# working.net
KiCad netlist of a schematic drawn in EAGLE
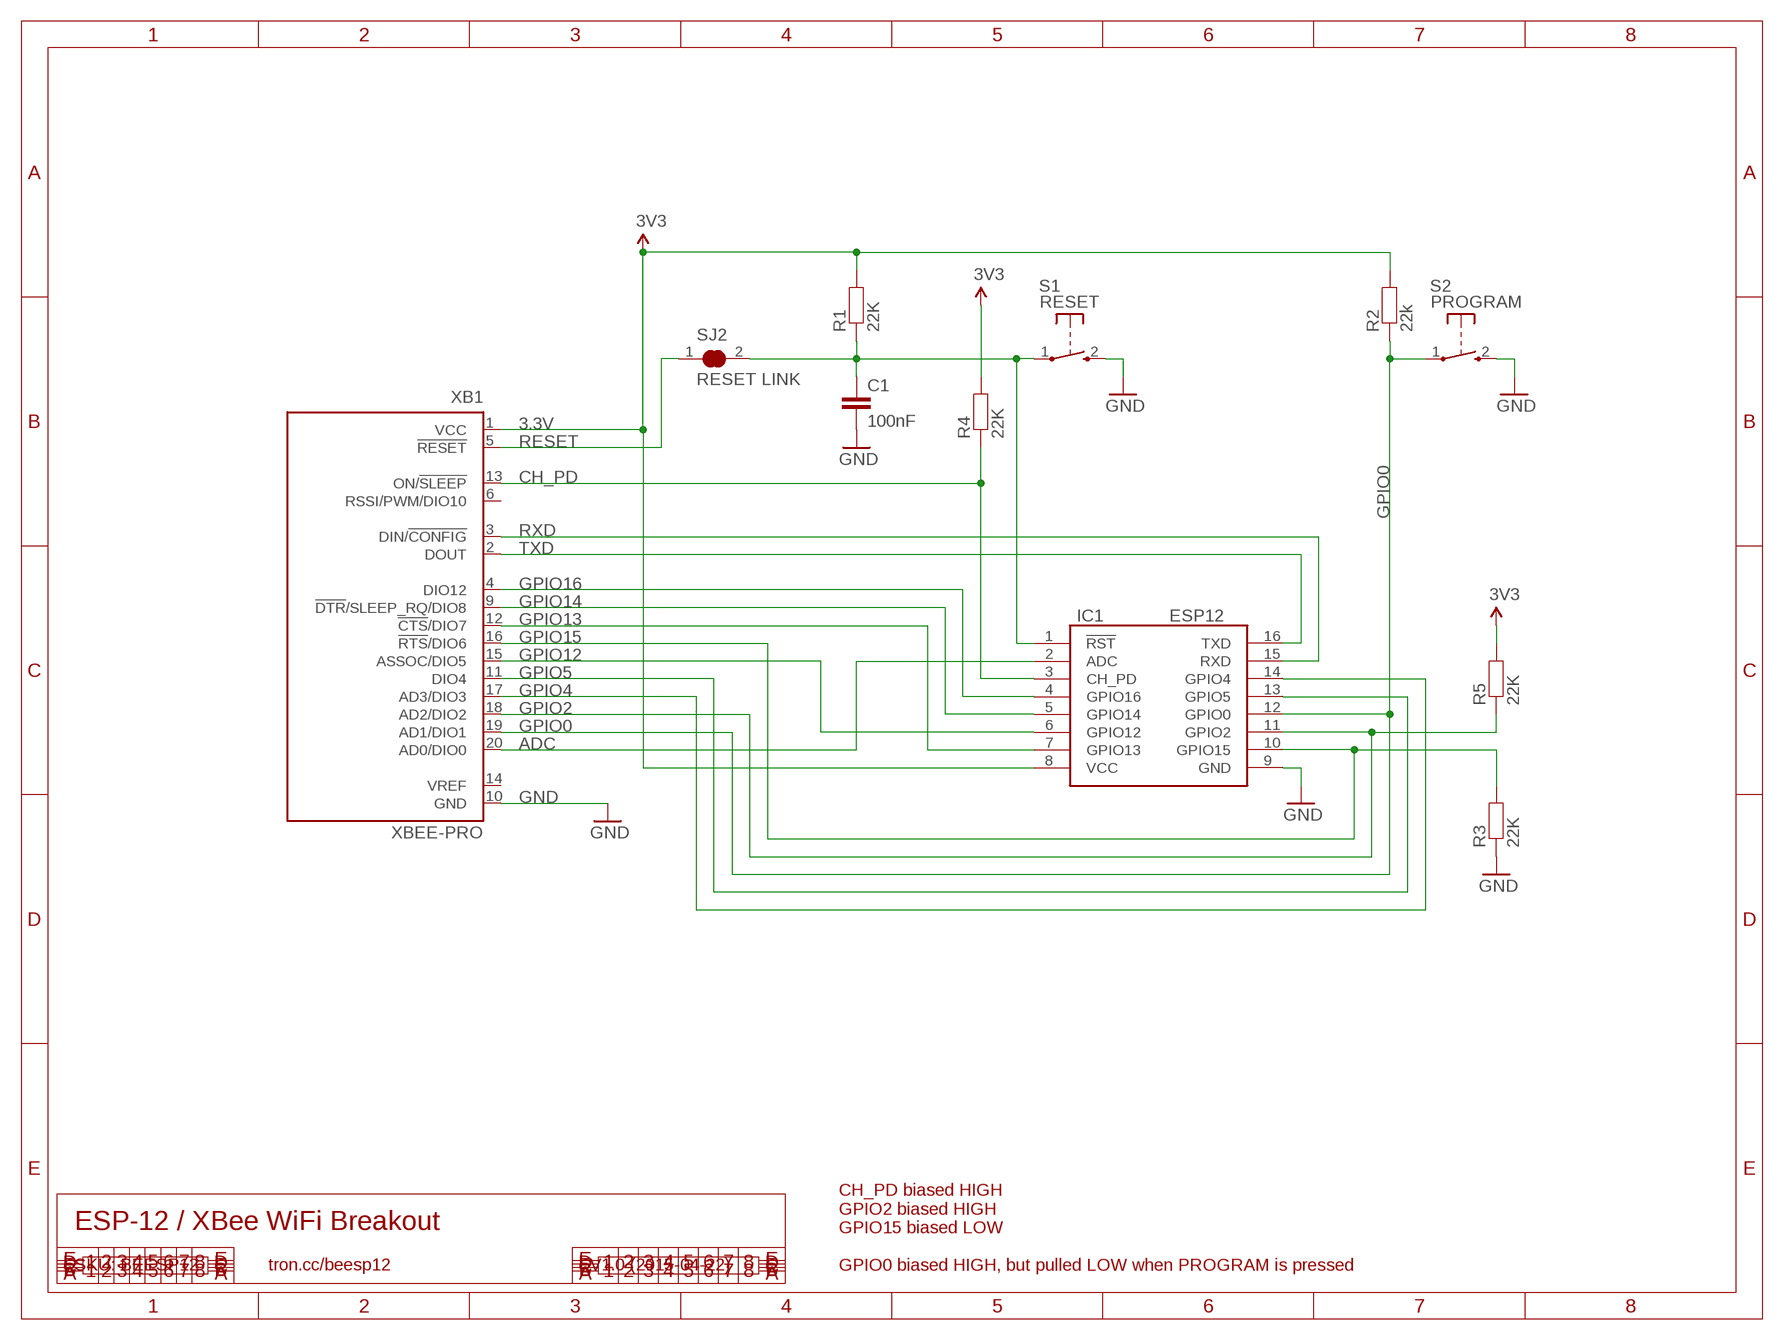
[diagram p0: schematic, sheet 1]

(export (version "E")
  (design (tool "Eeschema 10.0.6"))
  (components
    (comp (ref "C1")
      (value "100nF")
      (footprint "eagle-import:0603")
      (libsource (lib "eagle-import") (part "CAP0603"))
    )
    (comp (ref "IC1")
      (value "ESP12")
      (footprint "eagle-import:ESP12")
      (libsource (lib "eagle-import") (part "ESP12"))
    )
    (comp (ref "R1")
      (value "22K")
      (footprint "eagle-import:0603")
      (libsource (lib "eagle-import") (part "RESISTOR0603"))
    )
    (comp (ref "R2")
      (value "22k")
      (footprint "eagle-import:0603")
      (libsource (lib "eagle-import") (part "RESISTOR0603"))
    )
    (comp (ref "R3")
      (value "22K")
      (footprint "eagle-import:0603")
      (libsource (lib "eagle-import") (part "RESISTOR0603"))
    )
    (comp (ref "R4")
      (value "22K")
      (footprint "eagle-import:0603")
      (libsource (lib "eagle-import") (part "RESISTOR0603"))
    )
    (comp (ref "R5")
      (value "22K")
      (footprint "eagle-import:0603")
      (libsource (lib "eagle-import") (part "RESISTOR0603"))
    )
    (comp (ref "S1")
      (value "RESET")
      (footprint "eagle-import:TACTILE_SWITCH_SMD_2PIN_TINY")
      (libsource (lib "eagle-import") (part "TAC_SWITCH_2PIN"))
    )
    (comp (ref "S2")
      (value "PROGRAM")
      (footprint "eagle-import:TACTILE_SWITCH_SMD_2PIN_TINY")
      (libsource (lib "eagle-import") (part "TAC_SWITCH_2PIN"))
    )
    (comp (ref "SJ2")
      (value "RESET LINK")
      (footprint "eagle-import:SJC")
      (libsource (lib "eagle-import") (part "SJCN"))
    )
    (comp (ref "XB1")
      (value "XBEE-PRO")
      (footprint "eagle-import:XBEE-PRO")
      (fields (field (name "MPN") "XBP24-AWI-001"))
      (libsource (lib "eagle-import") (part "XBEE-PRO"))
    )
  )
  (nets
    (net (code "1") (name "/ADC") (class "Default")
      (node (ref "IC1") (pin "2") (pinfunction "ADC_2") (pintype "input"))
      (node (ref "XB1") (pin "20") (pinfunction "AD0/DIO0_20") (pintype "bidirectional"))
    )
    (net (code "2") (name "/CH_PD") (class "Default")
      (node (ref "IC1") (pin "3") (pinfunction "CH_PD_3") (pintype "input"))
      (node (ref "R4") (pin "1") (pinfunction "1_1") (pintype "passive"))
      (node (ref "XB1") (pin "13") (pinfunction "ON/~{SLEEP}_13") (pintype "output"))
    )
    (net (code "3") (name "/GPIO0") (class "Default")
      (node (ref "IC1") (pin "12") (pinfunction "GPIO0_12") (pintype "bidirectional"))
      (node (ref "R2") (pin "1") (pinfunction "1_1") (pintype "passive"))
      (node (ref "S2") (pin "1") (pinfunction "P_1") (pintype "passive"))
      (node (ref "XB1") (pin "19") (pinfunction "AD1/DIO1_19") (pintype "bidirectional"))
    )
    (net (code "4") (name "/GPIO2") (class "Default")
      (node (ref "IC1") (pin "11") (pinfunction "GPIO2_11") (pintype "bidirectional"))
      (node (ref "R5") (pin "1") (pinfunction "1_1") (pintype "passive"))
      (node (ref "XB1") (pin "18") (pinfunction "AD2/DIO2_18") (pintype "bidirectional"))
    )
    (net (code "5") (name "/GPIO4") (class "Default")
      (node (ref "IC1") (pin "14") (pinfunction "GPIO4_14") (pintype "bidirectional"))
      (node (ref "XB1") (pin "17") (pinfunction "AD3/DIO3_17") (pintype "bidirectional"))
    )
    (net (code "6") (name "/GPIO5") (class "Default")
      (node (ref "IC1") (pin "13") (pinfunction "GPIO5_13") (pintype "bidirectional"))
      (node (ref "XB1") (pin "11") (pinfunction "DIO4_11") (pintype "bidirectional"))
    )
    (net (code "7") (name "/GPIO12") (class "Default")
      (node (ref "IC1") (pin "6") (pinfunction "GPIO12_6") (pintype "bidirectional"))
      (node (ref "XB1") (pin "15") (pinfunction "ASSOC/DIO5_15") (pintype "bidirectional"))
    )
    (net (code "8") (name "/GPIO13") (class "Default")
      (node (ref "IC1") (pin "7") (pinfunction "GPIO13_7") (pintype "bidirectional"))
      (node (ref "XB1") (pin "12") (pinfunction "~{CTS}/DIO7_12") (pintype "bidirectional"))
    )
    (net (code "9") (name "/GPIO14") (class "Default")
      (node (ref "IC1") (pin "5") (pinfunction "GPIO14_5") (pintype "bidirectional"))
      (node (ref "XB1") (pin "9") (pinfunction "~{DTR}/SLEEP_RQ/DIO8_9") (pintype "bidirectional"))
    )
    (net (code "10") (name "/GPIO15") (class "Default")
      (node (ref "IC1") (pin "10") (pinfunction "GPIO15_10") (pintype "bidirectional"))
      (node (ref "R3") (pin "2") (pinfunction "2_2") (pintype "passive"))
      (node (ref "XB1") (pin "16") (pinfunction "~{RTS}/DIO6_16") (pintype "bidirectional"))
    )
    (net (code "11") (name "/GPIO16") (class "Default")
      (node (ref "IC1") (pin "4") (pinfunction "GPIO16_4") (pintype "bidirectional"))
      (node (ref "XB1") (pin "4") (pinfunction "DIO12_4") (pintype "bidirectional"))
    )
    (net (code "12") (name "/RESET") (class "Default")
      (node (ref "SJ2") (pin "1") (pinfunction "1_1") (pintype "passive"))
      (node (ref "XB1") (pin "5") (pinfunction "~{RESET}_5") (pintype "input"))
    )
    (net (code "13") (name "/RXD") (class "Default")
      (node (ref "IC1") (pin "15") (pinfunction "RXD_15") (pintype "input"))
      (node (ref "XB1") (pin "3") (pinfunction "DIN/~{CONFIG}_3") (pintype "input"))
    )
    (net (code "14") (name "/TXD") (class "Default")
      (node (ref "IC1") (pin "16") (pinfunction "TXD_16") (pintype "output"))
      (node (ref "XB1") (pin "2") (pinfunction "DOUT_2") (pintype "output"))
    )
    (net (code "15") (name "3V3") (class "Default")
      (node (ref "IC1") (pin "8") (pinfunction "VCC_8") (pintype "power_in"))
      (node (ref "R1") (pin "2") (pinfunction "2_2") (pintype "passive"))
      (node (ref "R2") (pin "2") (pinfunction "2_2") (pintype "passive"))
      (node (ref "R4") (pin "2") (pinfunction "2_2") (pintype "passive"))
      (node (ref "R5") (pin "2") (pinfunction "2_2") (pintype "passive"))
      (node (ref "XB1") (pin "1") (pinfunction "VCC_1") (pintype "power_in"))
    )
    (net (code "16") (name "GND") (class "Default")
      (node (ref "C1") (pin "2") (pinfunction "2_2") (pintype "passive"))
      (node (ref "IC1") (pin "9") (pinfunction "GND_9") (pintype "power_in"))
      (node (ref "R3") (pin "1") (pinfunction "1_1") (pintype "passive"))
      (node (ref "S1") (pin "2") (pinfunction "S_2") (pintype "passive"))
      (node (ref "S2") (pin "2") (pinfunction "S_2") (pintype "passive"))
      (node (ref "XB1") (pin "10") (pinfunction "GND_10") (pintype "power_in"))
    )
    (net (code "17") (name "Net-(IC1-~{RST})") (class "Default")
      (node (ref "C1") (pin "1") (pinfunction "1_1") (pintype "passive"))
      (node (ref "IC1") (pin "1") (pinfunction "~{RST}_1") (pintype "bidirectional"))
      (node (ref "R1") (pin "1") (pinfunction "1_1") (pintype "passive"))
      (node (ref "S1") (pin "1") (pinfunction "P_1") (pintype "passive"))
      (node (ref "SJ2") (pin "2") (pinfunction "2_2") (pintype "passive"))
    )
    (net (code "18") (name "unconnected-(XB1-RSSI{slash}PWM{slash}DIO10-Pad6)") (class "Default")
      (node (ref "XB1") (pin "6") (pinfunction "RSSI/PWM/DIO10_6") (pintype "output"))
    )
    (net (code "19") (name "unconnected-(XB1-VREF-Pad14)") (class "Default")
      (node (ref "XB1") (pin "14") (pinfunction "VREF_14") (pintype "input"))
    )
  )
)
